# uv-dosimeter-featherwing-mk-1_1.net
KiCad netlist of a schematic drawn in EAGLE
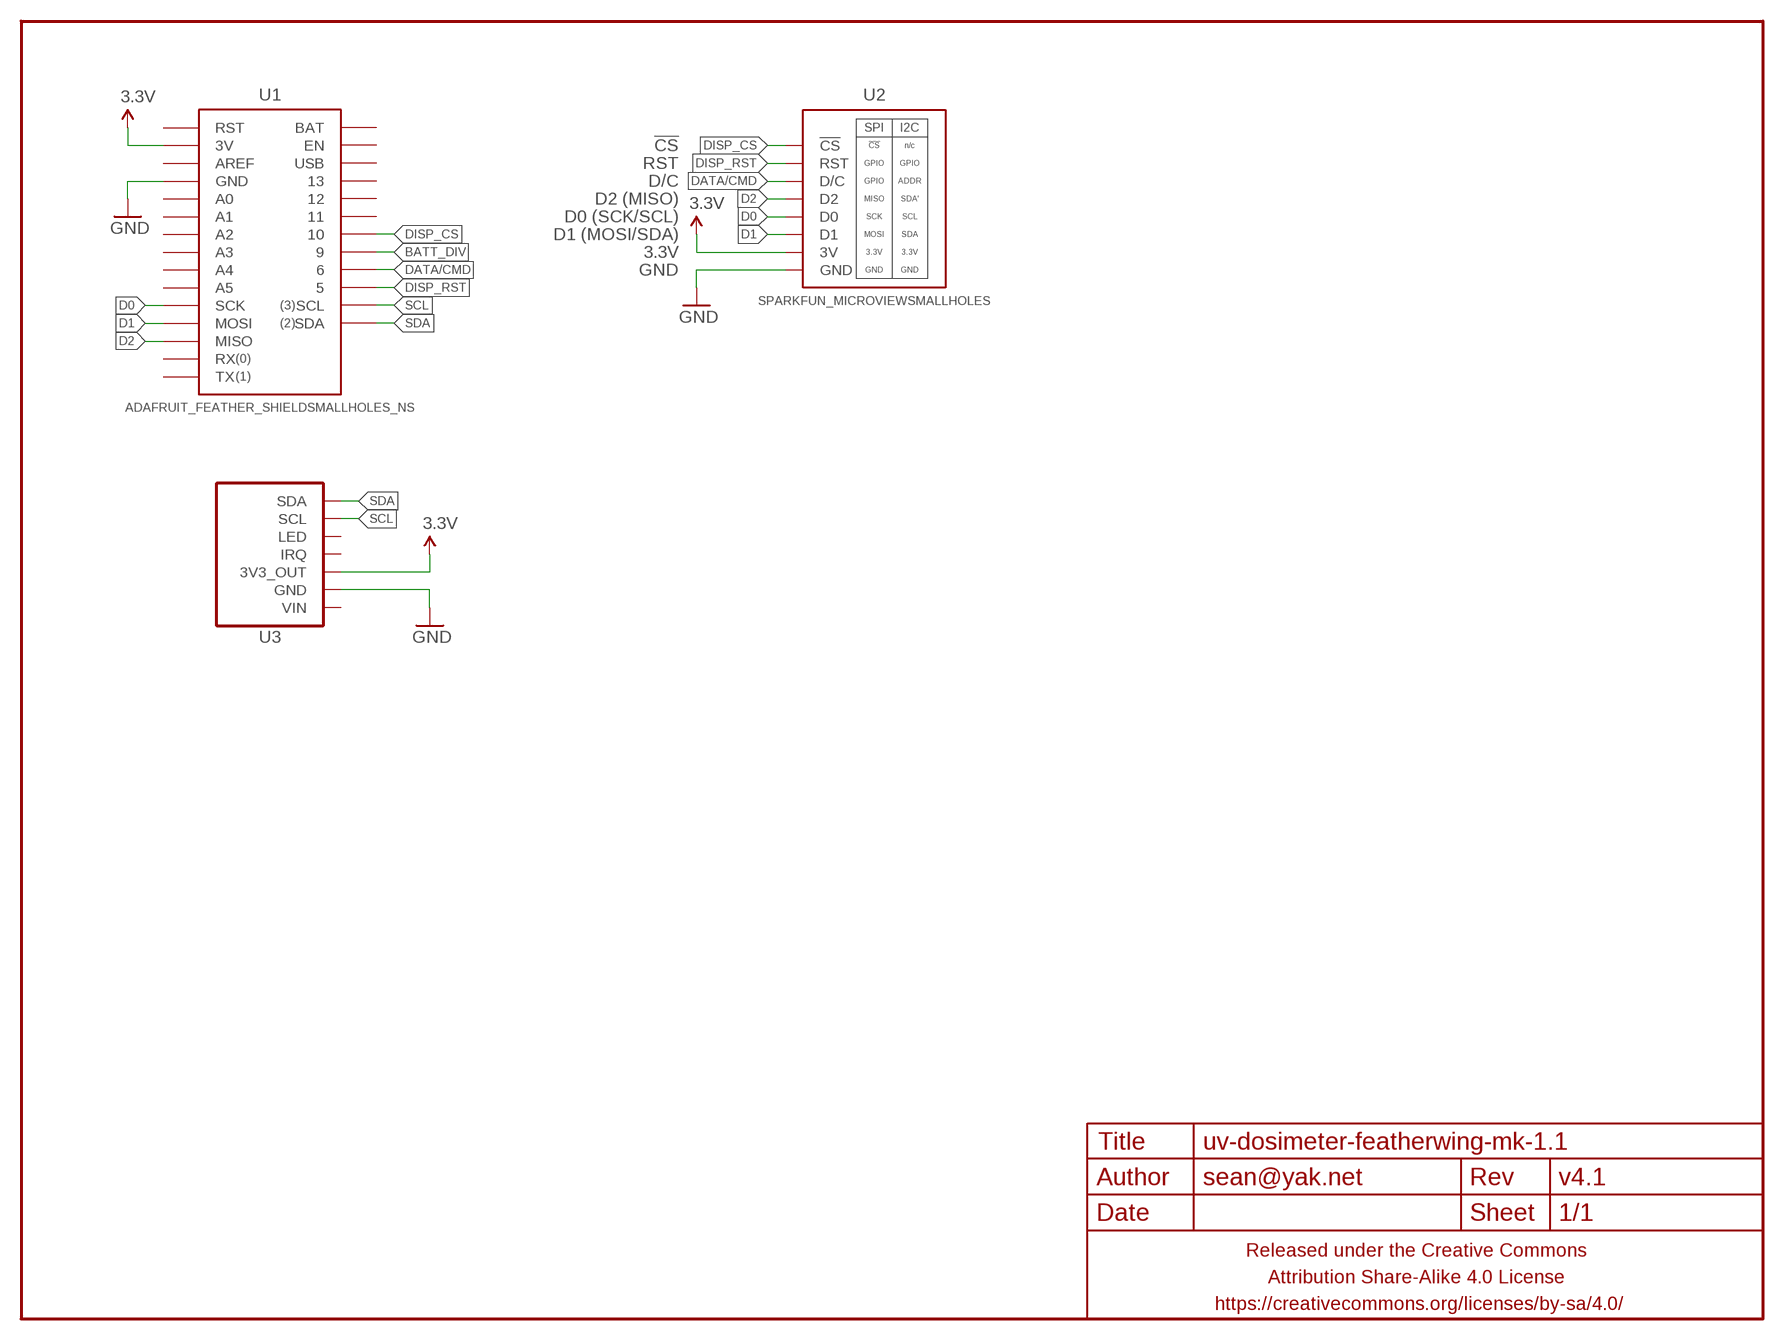
[diagram p0: schematic, sheet 1]

(export (version "E")
  (design (tool "Eeschema 10.0.6"))
  (components
    (comp (ref "FRAME1")
      (value "FRAME-LETTERNO_PACKAGE")
      (footprint "eagle-import:DUMMY")
      (fields (field (name "DESIGNER") "sean@yak.net") (field (name "VERSION") "v4.1"))
      (libsource (lib "eagle-import") (part "FRAME-LETTERNO_PACKAGE"))
    )
    (comp (ref "U1")
      (value "ADAFRUIT_FEATHER_SHIELDSMALLHOLES_NS")
      (footprint "eagle-import:ADAFRUIT_FEATHER_SMALLHOLES_NS")
      (libsource (lib "eagle-import") (part "ADAFRUIT_FEATHER_SHIELDSMALLHOLES_NS"))
    )
    (comp (ref "U2")
      (value "SPARKFUN_MICROVIEWSMALLHOLES")
      (footprint "eagle-import:SPARKFUN-MICROVIEW-SMALLHOLES")
      (libsource (lib "eagle-import") (part "SPARKFUN_MICROVIEWSMALLHOLES"))
    )
    (comp (ref "U3")
      (value "ADAFRUIT-SI1145-BREAKOUTSMALLHOLES")
      (footprint "eagle-import:ADAFRUIT-SI1145-BREAKOUT-LESSSILK-SMALLHOLES")
      (libsource (lib "eagle-import") (part "ADAFRUIT-SI1145-BREAKOUTSMALLHOLES"))
    )
  )
  (nets
    (net (code "1") (name "3.3V") (class "Default")
      (node (ref "U1") (pin "3V") (pinfunction "3V_3V") (pintype "bidirectional"))
      (node (ref "U2") (pin "3V") (pinfunction "3V_3V") (pintype "bidirectional"))
      (node (ref "U3") (pin "3V3_OUT") (pinfunction "3V3_OUT_3V3_OUT") (pintype "passive"))
    )
    (net (code "2") (name "BATT_DIV") (class "Default")
      (node (ref "U1") (pin "9") (pinfunction "9_9") (pintype "bidirectional"))
    )
    (net (code "3") (name "D0") (class "Default")
      (node (ref "U1") (pin "SCK") (pinfunction "SCK_SCK") (pintype "bidirectional"))
      (node (ref "U2") (pin "D0") (pinfunction "D0_D0") (pintype "bidirectional"))
    )
    (net (code "4") (name "D1") (class "Default")
      (node (ref "U1") (pin "MOSI") (pinfunction "MOSI_MOSI") (pintype "bidirectional"))
      (node (ref "U2") (pin "D1") (pinfunction "D1_D1") (pintype "bidirectional"))
    )
    (net (code "5") (name "D2") (class "Default")
      (node (ref "U1") (pin "MISO") (pinfunction "MISO_MISO") (pintype "bidirectional"))
      (node (ref "U2") (pin "D2") (pinfunction "D2_D2") (pintype "bidirectional"))
    )
    (net (code "6") (name "DATA{slash}CMD") (class "Default")
      (node (ref "U1") (pin "6") (pinfunction "6_6") (pintype "bidirectional"))
      (node (ref "U2") (pin "D/C") (pinfunction "D/C_D/C") (pintype "bidirectional"))
    )
    (net (code "7") (name "DISP_CS") (class "Default")
      (node (ref "U1") (pin "10") (pinfunction "10_10") (pintype "bidirectional"))
      (node (ref "U2") (pin "CS") (pinfunction "~{CS}_CS") (pintype "bidirectional"))
    )
    (net (code "8") (name "DISP_RST") (class "Default")
      (node (ref "U1") (pin "5") (pinfunction "5_5") (pintype "bidirectional"))
      (node (ref "U2") (pin "RST") (pinfunction "RST_RST") (pintype "bidirectional"))
    )
    (net (code "9") (name "GND") (class "Default")
      (node (ref "U1") (pin "GND@0") (pinfunction "GND_GND@0") (pintype "bidirectional"))
      (node (ref "U1") (pin "GND@1") (pinfunction "GND_GND@1") (pintype "bidirectional"))
      (node (ref "U2") (pin "GND") (pinfunction "GND_GND") (pintype "bidirectional"))
      (node (ref "U3") (pin "GND") (pinfunction "GND_GND") (pintype "passive"))
    )
    (net (code "10") (name "SCL") (class "Default")
      (node (ref "U1") (pin "SCL") (pinfunction "SCL_SCL") (pintype "bidirectional"))
      (node (ref "U3") (pin "SCL") (pinfunction "SCL_SCL") (pintype "passive"))
    )
    (net (code "11") (name "SDA") (class "Default")
      (node (ref "U1") (pin "SDA") (pinfunction "SDA_SDA") (pintype "bidirectional"))
      (node (ref "U3") (pin "SDA") (pinfunction "SDA_SDA") (pintype "passive"))
    )
    (net (code "12") (name "unconnected-(U1-Pad11)") (class "Default")
      (node (ref "U1") (pin "11") (pinfunction "11_11") (pintype "bidirectional"))
    )
    (net (code "13") (name "unconnected-(U1-Pad12)") (class "Default")
      (node (ref "U1") (pin "12") (pinfunction "12_12") (pintype "bidirectional"))
    )
    (net (code "14") (name "unconnected-(U1-Pad13)") (class "Default")
      (node (ref "U1") (pin "13") (pinfunction "13_13") (pintype "bidirectional"))
    )
    (net (code "15") (name "unconnected-(U1-PadA0)") (class "Default")
      (node (ref "U1") (pin "A0") (pinfunction "A0_A0") (pintype "bidirectional"))
    )
    (net (code "16") (name "unconnected-(U1-PadA1)") (class "Default")
      (node (ref "U1") (pin "A1") (pinfunction "A1_A1") (pintype "bidirectional"))
    )
    (net (code "17") (name "unconnected-(U1-PadA2)") (class "Default")
      (node (ref "U1") (pin "A2") (pinfunction "A2_A2") (pintype "bidirectional"))
    )
    (net (code "18") (name "unconnected-(U1-PadA3)") (class "Default")
      (node (ref "U1") (pin "A3") (pinfunction "A3_A3") (pintype "bidirectional"))
    )
    (net (code "19") (name "unconnected-(U1-PadA4)") (class "Default")
      (node (ref "U1") (pin "A4") (pinfunction "A4_A4") (pintype "bidirectional"))
    )
    (net (code "20") (name "unconnected-(U1-PadA5)") (class "Default")
      (node (ref "U1") (pin "A5") (pinfunction "A5_A5") (pintype "bidirectional"))
    )
    (net (code "21") (name "unconnected-(U1-PadAREF)") (class "Default")
      (node (ref "U1") (pin "AREF") (pinfunction "AREF_AREF") (pintype "bidirectional"))
    )
    (net (code "22") (name "unconnected-(U1-PadBAT)") (class "Default")
      (node (ref "U1") (pin "BAT") (pinfunction "BAT_BAT") (pintype "bidirectional"))
    )
    (net (code "23") (name "unconnected-(U1-PadEN)") (class "Default")
      (node (ref "U1") (pin "EN") (pinfunction "EN_EN") (pintype "bidirectional"))
    )
    (net (code "24") (name "unconnected-(U1-PadRST)") (class "Default")
      (node (ref "U1") (pin "RST") (pinfunction "RST_RST") (pintype "bidirectional"))
    )
    (net (code "25") (name "unconnected-(U1-PadRX)") (class "Default")
      (node (ref "U1") (pin "RX") (pinfunction "RX_RX") (pintype "bidirectional"))
    )
    (net (code "26") (name "unconnected-(U1-PadTX)") (class "Default")
      (node (ref "U1") (pin "TX") (pinfunction "TX_TX") (pintype "bidirectional"))
    )
    (net (code "27") (name "unconnected-(U1-PadUSB)") (class "Default")
      (node (ref "U1") (pin "USB") (pinfunction "USB_USB") (pintype "bidirectional"))
    )
    (net (code "28") (name "unconnected-(U3-PadIRQ)") (class "Default")
      (node (ref "U3") (pin "IRQ") (pinfunction "IRQ_IRQ") (pintype "passive"))
    )
    (net (code "29") (name "unconnected-(U3-PadLED)") (class "Default")
      (node (ref "U3") (pin "LED") (pinfunction "LED_LED") (pintype "passive"))
    )
    (net (code "30") (name "unconnected-(U3-PadVIN)") (class "Default")
      (node (ref "U3") (pin "VIN") (pinfunction "VIN_VIN") (pintype "passive"))
    )
  )
)
